# me433_2.net
KiCad netlist of a schematic drawn in EAGLE
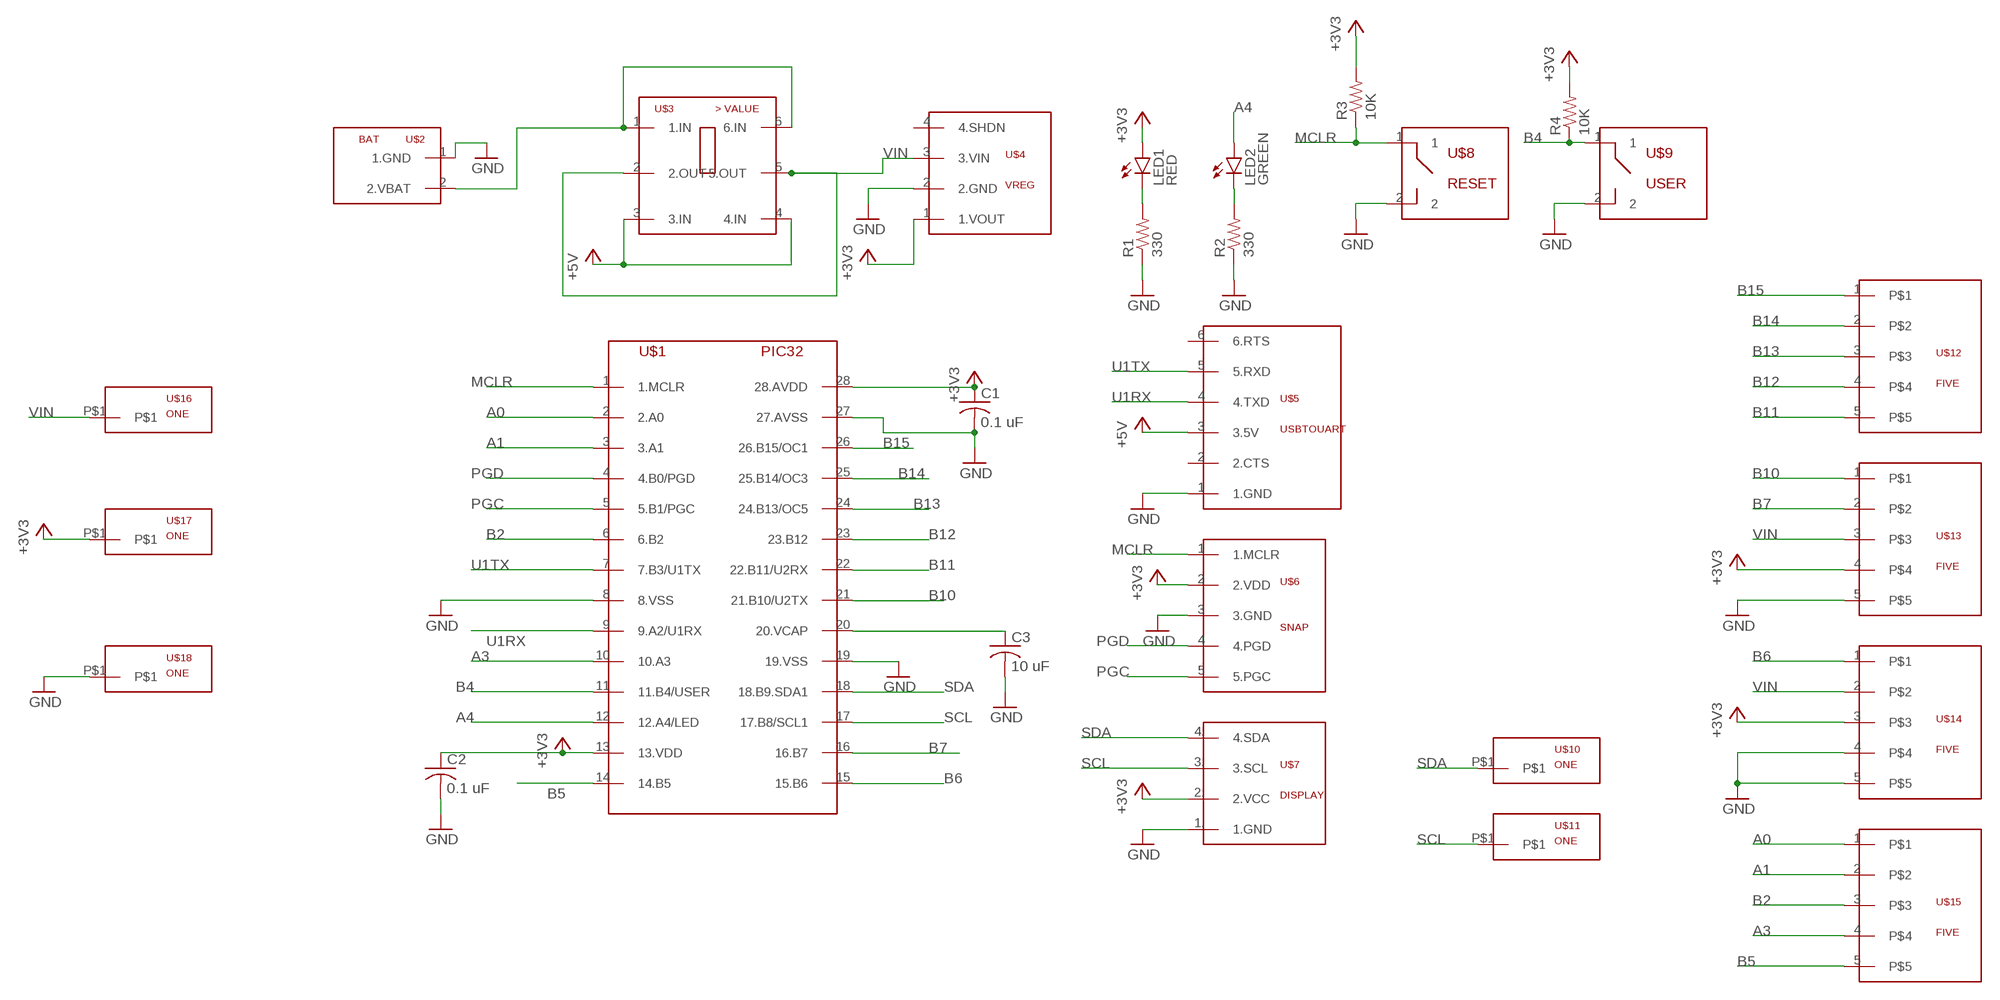
[diagram p0: schematic, sheet 1]

(export (version "E")
  (design (tool "Eeschema 10.0.6"))
  (components
    (comp (ref "C1")
      (value "0.1 uF")
      (footprint "eagle-import:C025-024X044")
      (libsource (lib "eagle-import") (part "C-US025-024X044"))
    )
    (comp (ref "C2")
      (value "0.1 uF")
      (footprint "eagle-import:C025-024X044")
      (libsource (lib "eagle-import") (part "C-US025-024X044"))
    )
    (comp (ref "C3")
      (value "10 uF")
      (footprint "eagle-import:C025-024X044")
      (libsource (lib "eagle-import") (part "C-US025-024X044"))
    )
    (comp (ref "LED1")
      (value "RED")
      (footprint "eagle-import:LED3MM")
      (libsource (lib "eagle-import") (part "LED3MM"))
    )
    (comp (ref "LED2")
      (value "GREEN")
      (footprint "eagle-import:LED3MM")
      (libsource (lib "eagle-import") (part "LED3MM"))
    )
    (comp (ref "R1")
      (value "330")
      (footprint "eagle-import:0207_7")
      (libsource (lib "eagle-import") (part "R-US_0207/7"))
    )
    (comp (ref "R2")
      (value "330")
      (footprint "eagle-import:0207_7")
      (libsource (lib "eagle-import") (part "R-US_0207/7"))
    )
    (comp (ref "R3")
      (value "10K")
      (footprint "eagle-import:0207_7")
      (libsource (lib "eagle-import") (part "R-US_0207/7"))
    )
    (comp (ref "R4")
      (value "10K")
      (footprint "eagle-import:0207_7")
      (libsource (lib "eagle-import") (part "R-US_0207/7"))
    )
    (comp (ref "U$1")
      (value "PIC32")
      (footprint "eagle-import:DIL28-3")
      (libsource (lib "eagle-import") (part "PIC32"))
    )
    (comp (ref "U$2")
      (value "BAT")
      (footprint "eagle-import:BAT")
      (libsource (lib "eagle-import") (part "BAT"))
    )
    (comp (ref "U$3")
      (value "SLIDE")
      (footprint "eagle-import:SLIDE")
      (libsource (lib "eagle-import") (part "SLIDE"))
    )
    (comp (ref "U$4")
      (value "VREG")
      (footprint "eagle-import:VREG")
      (libsource (lib "eagle-import") (part "VREG"))
    )
    (comp (ref "U$5")
      (value "USBTOUART")
      (footprint "eagle-import:USBTOUART")
      (libsource (lib "eagle-import") (part "USBTOUART"))
    )
    (comp (ref "U$6")
      (value "SNAP")
      (footprint "eagle-import:SNAP")
      (libsource (lib "eagle-import") (part "SNAP"))
    )
    (comp (ref "U$7")
      (value "DISPLAY")
      (footprint "eagle-import:DISPLAY")
      (libsource (lib "eagle-import") (part "DISPLAY"))
    )
    (comp (ref "U$8")
      (value "RESET")
      (footprint "eagle-import:BUTTON")
      (libsource (lib "eagle-import") (part "BUTTON"))
    )
    (comp (ref "U$9")
      (value "USER")
      (footprint "eagle-import:BUTTON")
      (libsource (lib "eagle-import") (part "BUTTON"))
    )
    (comp (ref "U$10")
      (value "ONE")
      (footprint "eagle-import:ONE")
      (libsource (lib "eagle-import") (part "ONE"))
    )
    (comp (ref "U$11")
      (value "ONE")
      (footprint "eagle-import:ONE")
      (libsource (lib "eagle-import") (part "ONE"))
    )
    (comp (ref "U$12")
      (value "FIVE")
      (footprint "eagle-import:FIVE")
      (libsource (lib "eagle-import") (part "FIVE"))
    )
    (comp (ref "U$13")
      (value "FIVE")
      (footprint "eagle-import:FIVE")
      (libsource (lib "eagle-import") (part "FIVE"))
    )
    (comp (ref "U$14")
      (value "FIVE")
      (footprint "eagle-import:FIVE")
      (libsource (lib "eagle-import") (part "FIVE"))
    )
    (comp (ref "U$15")
      (value "FIVE")
      (footprint "eagle-import:FIVE")
      (libsource (lib "eagle-import") (part "FIVE"))
    )
    (comp (ref "U$16")
      (value "ONE")
      (footprint "eagle-import:ONE")
      (libsource (lib "eagle-import") (part "ONE"))
    )
    (comp (ref "U$17")
      (value "ONE")
      (footprint "eagle-import:ONE")
      (libsource (lib "eagle-import") (part "ONE"))
    )
    (comp (ref "U$18")
      (value "ONE")
      (footprint "eagle-import:ONE")
      (libsource (lib "eagle-import") (part "ONE"))
    )
  )
  (nets
    (net (code "1") (name "+3V3") (class "Default")
      (node (ref "C1") (pin "1") (pinfunction "1_1") (pintype "passive"))
      (node (ref "C2") (pin "1") (pinfunction "1_1") (pintype "passive"))
      (node (ref "LED1") (pin "A") (pinfunction "A_A") (pintype "passive"))
      (node (ref "R3") (pin "2") (pinfunction "2_2") (pintype "passive"))
      (node (ref "R4") (pin "2") (pinfunction "2_2") (pintype "passive"))
      (node (ref "U$1") (pin "13") (pinfunction "13.VDD_13") (pintype "bidirectional"))
      (node (ref "U$1") (pin "28") (pinfunction "28.AVDD_28") (pintype "bidirectional"))
      (node (ref "U$13") (pin "4") (pinfunction "P$4_4") (pintype "bidirectional"))
      (node (ref "U$14") (pin "3") (pinfunction "P$3_3") (pintype "bidirectional"))
      (node (ref "U$17") (pin "P$1") (pinfunction "P$1_P$1") (pintype "bidirectional"))
      (node (ref "U$4") (pin "1") (pinfunction "1.VOUT_1") (pintype "bidirectional"))
      (node (ref "U$6") (pin "2") (pinfunction "2.VDD_2") (pintype "bidirectional"))
      (node (ref "U$7") (pin "2.") (pinfunction "2.VCC_2.") (pintype "bidirectional"))
    )
    (net (code "2") (name "+5V") (class "Default")
      (node (ref "U$3") (pin "3") (pinfunction "3.IN_3") (pintype "bidirectional"))
      (node (ref "U$3") (pin "4") (pinfunction "4.IN_4") (pintype "bidirectional"))
      (node (ref "U$5") (pin "3") (pinfunction "3.5V_3") (pintype "bidirectional"))
    )
    (net (code "3") (name "/A0") (class "Default")
      (node (ref "U$1") (pin "2") (pinfunction "2.A0_2") (pintype "bidirectional"))
      (node (ref "U$15") (pin "1") (pinfunction "P$1_1") (pintype "bidirectional"))
    )
    (net (code "4") (name "/A1") (class "Default")
      (node (ref "U$1") (pin "3") (pinfunction "3.A1_3") (pintype "bidirectional"))
      (node (ref "U$15") (pin "2") (pinfunction "P$2_2") (pintype "bidirectional"))
    )
    (net (code "5") (name "/A3") (class "Default")
      (node (ref "U$1") (pin "10") (pinfunction "10.A3_10") (pintype "bidirectional"))
      (node (ref "U$15") (pin "4") (pinfunction "P$4_4") (pintype "bidirectional"))
    )
    (net (code "6") (name "/A4") (class "Default")
      (node (ref "LED2") (pin "A") (pinfunction "A_A") (pintype "passive"))
      (node (ref "U$1") (pin "12") (pinfunction "12.A4/LED_12") (pintype "bidirectional"))
    )
    (net (code "7") (name "/B2") (class "Default")
      (node (ref "U$1") (pin "6") (pinfunction "6.B2_6") (pintype "bidirectional"))
      (node (ref "U$15") (pin "3") (pinfunction "P$3_3") (pintype "bidirectional"))
    )
    (net (code "8") (name "/B4") (class "Default")
      (node (ref "R4") (pin "1") (pinfunction "1_1") (pintype "passive"))
      (node (ref "U$1") (pin "11") (pinfunction "11.B4/USER_11") (pintype "bidirectional"))
      (node (ref "U$9") (pin "1") (pinfunction "1_1") (pintype "bidirectional"))
    )
    (net (code "9") (name "/B5") (class "Default")
      (node (ref "U$1") (pin "14") (pinfunction "14.B5_14") (pintype "bidirectional"))
      (node (ref "U$15") (pin "5") (pinfunction "P$5_5") (pintype "bidirectional"))
    )
    (net (code "10") (name "/B6") (class "Default")
      (node (ref "U$1") (pin "15") (pinfunction "15.B6_15") (pintype "bidirectional"))
      (node (ref "U$14") (pin "1") (pinfunction "P$1_1") (pintype "bidirectional"))
    )
    (net (code "11") (name "/B7") (class "Default")
      (node (ref "U$1") (pin "16") (pinfunction "16.B7_16") (pintype "bidirectional"))
      (node (ref "U$13") (pin "2") (pinfunction "P$2_2") (pintype "bidirectional"))
    )
    (net (code "12") (name "/B10") (class "Default")
      (node (ref "U$1") (pin "21") (pinfunction "21.B10/U2TX_21") (pintype "bidirectional"))
      (node (ref "U$13") (pin "1") (pinfunction "P$1_1") (pintype "bidirectional"))
    )
    (net (code "13") (name "/B11") (class "Default")
      (node (ref "U$1") (pin "22") (pinfunction "22.B11/U2RX_22") (pintype "bidirectional"))
      (node (ref "U$12") (pin "5") (pinfunction "P$5_5") (pintype "bidirectional"))
    )
    (net (code "14") (name "/B12") (class "Default")
      (node (ref "U$1") (pin "23") (pinfunction "23.B12_23") (pintype "bidirectional"))
      (node (ref "U$12") (pin "4") (pinfunction "P$4_4") (pintype "bidirectional"))
    )
    (net (code "15") (name "/B13") (class "Default")
      (node (ref "U$1") (pin "24") (pinfunction "24.B13/OC5_24") (pintype "bidirectional"))
      (node (ref "U$12") (pin "3") (pinfunction "P$3_3") (pintype "bidirectional"))
    )
    (net (code "16") (name "/B14") (class "Default")
      (node (ref "U$1") (pin "25") (pinfunction "25.B14/OC3_25") (pintype "bidirectional"))
      (node (ref "U$12") (pin "2") (pinfunction "P$2_2") (pintype "bidirectional"))
    )
    (net (code "17") (name "/B15") (class "Default")
      (node (ref "U$1") (pin "26") (pinfunction "26.B15/OC1_26") (pintype "bidirectional"))
      (node (ref "U$12") (pin "1") (pinfunction "P$1_1") (pintype "bidirectional"))
    )
    (net (code "18") (name "/MCLR") (class "Default")
      (node (ref "R3") (pin "1") (pinfunction "1_1") (pintype "passive"))
      (node (ref "U$1") (pin "1") (pinfunction "1.MCLR_1") (pintype "bidirectional"))
      (node (ref "U$6") (pin "1") (pinfunction "1.MCLR_1") (pintype "bidirectional"))
      (node (ref "U$8") (pin "1") (pinfunction "1_1") (pintype "bidirectional"))
    )
    (net (code "19") (name "/PGC") (class "Default")
      (node (ref "U$1") (pin "5") (pinfunction "5.B1/PGC_5") (pintype "bidirectional"))
      (node (ref "U$6") (pin "5") (pinfunction "5.PGC_5") (pintype "bidirectional"))
    )
    (net (code "20") (name "/PGD") (class "Default")
      (node (ref "U$1") (pin "4") (pinfunction "4.B0/PGD_4") (pintype "bidirectional"))
      (node (ref "U$6") (pin "4") (pinfunction "4.PGD_4") (pintype "bidirectional"))
    )
    (net (code "21") (name "/SCL") (class "Default")
      (node (ref "U$1") (pin "17") (pinfunction "17.B8/SCL1_17") (pintype "bidirectional"))
      (node (ref "U$11") (pin "P$1") (pinfunction "P$1_P$1") (pintype "bidirectional"))
      (node (ref "U$7") (pin "3.") (pinfunction "3.SCL_3.") (pintype "bidirectional"))
    )
    (net (code "22") (name "/SDA") (class "Default")
      (node (ref "U$1") (pin "18") (pinfunction "18.B9.SDA1_18") (pintype "bidirectional"))
      (node (ref "U$10") (pin "P$1") (pinfunction "P$1_P$1") (pintype "bidirectional"))
      (node (ref "U$7") (pin "4.") (pinfunction "4.SDA_4.") (pintype "bidirectional"))
    )
    (net (code "23") (name "/U1RX") (class "Default")
      (node (ref "U$1") (pin "9") (pinfunction "9.A2/U1RX_9") (pintype "bidirectional"))
      (node (ref "U$5") (pin "4") (pinfunction "4.TXD_4") (pintype "bidirectional"))
    )
    (net (code "24") (name "/U1TX") (class "Default")
      (node (ref "U$1") (pin "7") (pinfunction "7.B3/U1TX_7") (pintype "bidirectional"))
      (node (ref "U$5") (pin "5") (pinfunction "5.RXD_5") (pintype "bidirectional"))
    )
    (net (code "25") (name "/VIN") (class "Default")
      (node (ref "U$13") (pin "3") (pinfunction "P$3_3") (pintype "bidirectional"))
      (node (ref "U$14") (pin "2") (pinfunction "P$2_2") (pintype "bidirectional"))
      (node (ref "U$16") (pin "P$1") (pinfunction "P$1_P$1") (pintype "bidirectional"))
      (node (ref "U$3") (pin "2") (pinfunction "2.OUT_2") (pintype "bidirectional"))
      (node (ref "U$3") (pin "5") (pinfunction "5.OUT_5") (pintype "bidirectional"))
      (node (ref "U$4") (pin "3") (pinfunction "3.VIN_3") (pintype "bidirectional"))
    )
    (net (code "26") (name "GND") (class "Default")
      (node (ref "C1") (pin "2") (pinfunction "2_2") (pintype "passive"))
      (node (ref "C2") (pin "2") (pinfunction "2_2") (pintype "passive"))
      (node (ref "C3") (pin "2") (pinfunction "2_2") (pintype "passive"))
      (node (ref "R1") (pin "1") (pinfunction "1_1") (pintype "passive"))
      (node (ref "R2") (pin "1") (pinfunction "1_1") (pintype "passive"))
      (node (ref "U$1") (pin "19") (pinfunction "19.VSS_19") (pintype "bidirectional"))
      (node (ref "U$1") (pin "27") (pinfunction "27.AVSS_27") (pintype "bidirectional"))
      (node (ref "U$1") (pin "8") (pinfunction "8.VSS_8") (pintype "bidirectional"))
      (node (ref "U$13") (pin "5") (pinfunction "P$5_5") (pintype "bidirectional"))
      (node (ref "U$14") (pin "4") (pinfunction "P$4_4") (pintype "bidirectional"))
      (node (ref "U$14") (pin "5") (pinfunction "P$5_5") (pintype "bidirectional"))
      (node (ref "U$18") (pin "P$1") (pinfunction "P$1_P$1") (pintype "bidirectional"))
      (node (ref "U$2") (pin "1") (pinfunction "1.GND_1") (pintype "bidirectional"))
      (node (ref "U$4") (pin "2") (pinfunction "2.GND_2") (pintype "bidirectional"))
      (node (ref "U$5") (pin "1") (pinfunction "1.GND_1") (pintype "bidirectional"))
      (node (ref "U$6") (pin "3") (pinfunction "3.GND_3") (pintype "bidirectional"))
      (node (ref "U$7") (pin "1.") (pinfunction "1.GND_1.") (pintype "bidirectional"))
      (node (ref "U$8") (pin "2") (pinfunction "2_2") (pintype "bidirectional"))
      (node (ref "U$9") (pin "2") (pinfunction "2_2") (pintype "bidirectional"))
    )
    (net (code "27") (name "Net-(LED1-C)") (class "Default")
      (node (ref "LED1") (pin "K") (pinfunction "C_K") (pintype "passive"))
      (node (ref "R1") (pin "2") (pinfunction "2_2") (pintype "passive"))
    )
    (net (code "28") (name "Net-(LED2-C)") (class "Default")
      (node (ref "LED2") (pin "K") (pinfunction "C_K") (pintype "passive"))
      (node (ref "R2") (pin "2") (pinfunction "2_2") (pintype "passive"))
    )
    (net (code "29") (name "Net-(U$1-20.VCAP)") (class "Default")
      (node (ref "C3") (pin "1") (pinfunction "1_1") (pintype "passive"))
      (node (ref "U$1") (pin "20") (pinfunction "20.VCAP_20") (pintype "bidirectional"))
    )
    (net (code "30") (name "Net-(U$2-2.VBAT)") (class "Default")
      (node (ref "U$2") (pin "2") (pinfunction "2.VBAT_2") (pintype "bidirectional"))
      (node (ref "U$3") (pin "1") (pinfunction "1.IN_1") (pintype "bidirectional"))
      (node (ref "U$3") (pin "6") (pinfunction "6.IN_6") (pintype "bidirectional"))
    )
    (net (code "31") (name "unconnected-(U$4-4.SHDN-Pad4)") (class "Default")
      (node (ref "U$4") (pin "4") (pinfunction "4.SHDN_4") (pintype "bidirectional"))
    )
    (net (code "32") (name "unconnected-(U$5-2.CTS-Pad2)") (class "Default")
      (node (ref "U$5") (pin "2") (pinfunction "2.CTS_2") (pintype "bidirectional"))
    )
    (net (code "33") (name "unconnected-(U$5-6.RTS-Pad6)") (class "Default")
      (node (ref "U$5") (pin "6") (pinfunction "6.RTS_6") (pintype "bidirectional"))
    )
  )
)
